# RTDsSheet3.net
KiCad netlist of a schematic drawn in Altium Designer
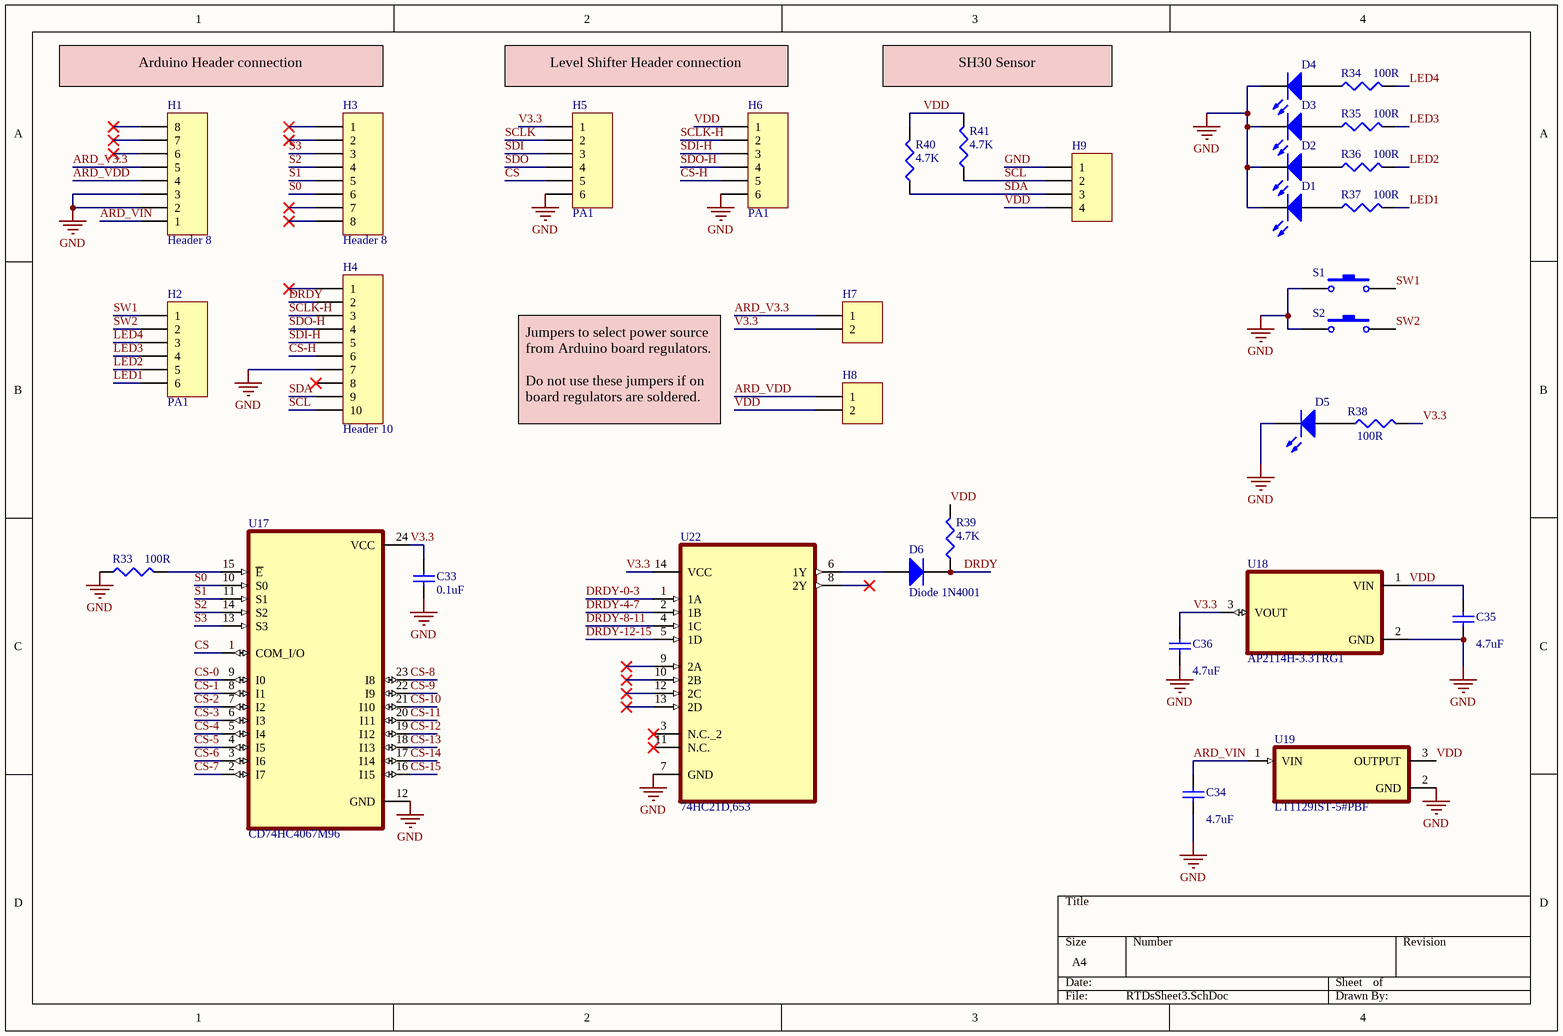
[diagram p0: RTDsSheet3.SchDoc]

(export (version "E")
  (design (tool "Eeschema 10.0.6"))
  (components
    (comp (ref "C33")
      (value "0.1uF")
      (footprint "1608[0603]")
      (description "Capacitor (Semiconductor SIM Model)")
      (fields (field (name "PUBLISHER") "Altium Limited"))
      (libsource (lib "Miscellaneous Devices") (part "Cap Semi"))
    )
    (comp (ref "C34")
      (value "4.7uF")
      (footprint "C0805")
      (description "Capacitor (Semiconductor SIM Model)")
      (fields (field (name "PUBLISHER") "Altium Limited"))
      (libsource (lib "Miscellaneous Devices") (part "Cap Semi"))
    )
    (comp (ref "C35")
      (value "4.7uF")
      (footprint "C0805")
      (description "Capacitor (Semiconductor SIM Model)")
      (fields (field (name "PUBLISHER") "Altium Limited"))
      (libsource (lib "Miscellaneous Devices") (part "Cap Semi"))
    )
    (comp (ref "C36")
      (value "4.7uF")
      (footprint "C0805")
      (description "Capacitor (Semiconductor SIM Model)")
      (fields (field (name "PUBLISHER") "Altium Limited"))
      (libsource (lib "Miscellaneous Devices") (part "Cap Semi"))
    )
    (comp (ref "D1")
      (value "~")
      (footprint "6-0805_N")
      (description "Typical BLUE SiC LED")
      (fields (field (name "PUBLISHER") "Altium Limited"))
      (libsource (lib "Miscellaneous Devices") (part "LED3"))
    )
    (comp (ref "D2")
      (value "~")
      (footprint "6-0805_N")
      (description "Typical BLUE SiC LED")
      (fields (field (name "PUBLISHER") "Altium Limited"))
      (libsource (lib "Miscellaneous Devices") (part "LED3"))
    )
    (comp (ref "D3")
      (value "~")
      (footprint "6-0805_N")
      (description "Typical BLUE SiC LED")
      (fields (field (name "PUBLISHER") "Altium Limited"))
      (libsource (lib "Miscellaneous Devices") (part "LED3"))
    )
    (comp (ref "D4")
      (value "~")
      (footprint "6-0805_N")
      (description "Typical BLUE SiC LED")
      (fields (field (name "PUBLISHER") "Altium Limited"))
      (libsource (lib "Miscellaneous Devices") (part "LED3"))
    )
    (comp (ref "D5")
      (value "~")
      (footprint "6-0805_N")
      (description "Typical BLUE SiC LED")
      (fields (field (name "PUBLISHER") "Altium Limited"))
      (libsource (lib "Miscellaneous Devices") (part "LED3"))
    )
    (comp (ref "D6")
      (value "Diode 1N4001")
      (footprint "C0805")
      (description "1 Amp General Purpose Rectifier")
      (fields (field (name "PUBLISHER") "Altium Limited"))
      (libsource (lib "Miscellaneous Devices") (part "Diode 1N4001"))
    )
    (comp (ref "H1")
      (value "Header 8")
      (footprint "HDR1X8")
      (description "Header, 8-Pin")
      (fields (field (name "PUBLISHER") "Altium Limited"))
      (libsource (lib "Miscellaneous Connectors") (part "Header 8"))
    )
    (comp (ref "H2")
      (value "PA1")
      (footprint "HDR1X6")
      (description "Header, 6-Pin")
      (fields (field (name "PUBLISHER") "Altium Limited"))
      (libsource (lib "Miscellaneous Connectors") (part "Header 6"))
    )
    (comp (ref "H3")
      (value "Header 8")
      (footprint "HDR1X8")
      (description "Header, 8-Pin")
      (fields (field (name "PUBLISHER") "Altium Limited"))
      (libsource (lib "") (part "Header 8_1"))
    )
    (comp (ref "H4")
      (value "Header 10")
      (footprint "HDR1X10")
      (description "Header, 10-Pin")
      (fields (field (name "PUBLISHER") "Altium Limited"))
      (libsource (lib "Miscellaneous Connectors") (part "Header 10"))
    )
    (comp (ref "H5")
      (value "PA1")
      (footprint "HDR1X6")
      (description "Header, 6-Pin")
      (fields (field (name "PUBLISHER") "Altium Limited"))
      (libsource (lib "Miscellaneous Connectors") (part "Header 6"))
    )
    (comp (ref "H6")
      (value "PA1")
      (footprint "HDR1X6")
      (description "Header, 6-Pin")
      (fields (field (name "PUBLISHER") "Altium Limited"))
      (libsource (lib "Miscellaneous Connectors") (part "Header 6"))
    )
    (comp (ref "H7")
      (value "~")
      (footprint "HDR1X2")
      (description "Header, 2-Pin")
      (fields (field (name "PUBLISHER") "Altium Limited"))
      (libsource (lib "Miscellaneous Connectors") (part "Header 2"))
    )
    (comp (ref "H8")
      (value "~")
      (footprint "HDR1X2")
      (description "Header, 2-Pin")
      (fields (field (name "PUBLISHER") "Altium Limited"))
      (libsource (lib "Miscellaneous Connectors") (part "Header 2"))
    )
    (comp (ref "H9")
      (value "~")
      (footprint "HDR1X4")
      (description "Header, 4-Pin")
      (fields (field (name "PUBLISHER") "Altium Limited"))
      (libsource (lib "Miscellaneous Connectors") (part "Header 4"))
    )
    (comp (ref "R33")
      (value "100R")
      (footprint "J1-0603")
      (description "Resistor")
      (fields (field (name "PUBLISHER") "Altium Limited"))
      (libsource (lib "Miscellaneous Devices") (part "Res3"))
    )
    (comp (ref "R34")
      (value "100R")
      (footprint "J1-0603")
      (description "Resistor")
      (fields (field (name "PUBLISHER") "Altium Limited"))
      (libsource (lib "Miscellaneous Devices") (part "Res3"))
    )
    (comp (ref "R35")
      (value "100R")
      (footprint "J1-0603")
      (description "Resistor")
      (fields (field (name "PUBLISHER") "Altium Limited"))
      (libsource (lib "Miscellaneous Devices") (part "Res3"))
    )
    (comp (ref "R36")
      (value "100R")
      (footprint "J1-0603")
      (description "Resistor")
      (fields (field (name "PUBLISHER") "Altium Limited"))
      (libsource (lib "Miscellaneous Devices") (part "Res3"))
    )
    (comp (ref "R37")
      (value "100R")
      (footprint "J1-0603")
      (description "Resistor")
      (fields (field (name "PUBLISHER") "Altium Limited"))
      (libsource (lib "Miscellaneous Devices") (part "Res3"))
    )
    (comp (ref "R38")
      (value "100R")
      (footprint "J1-0603")
      (description "Resistor")
      (fields (field (name "PUBLISHER") "Altium Limited"))
      (libsource (lib "Miscellaneous Devices") (part "Res3"))
    )
    (comp (ref "R39")
      (value "4.7K")
      (footprint "J1-0603")
      (description "Resistor")
      (fields (field (name "PUBLISHER") "Altium Limited"))
      (libsource (lib "Miscellaneous Devices") (part "Res3"))
    )
    (comp (ref "R40")
      (value "4.7K")
      (footprint "J1-0603")
      (description "Resistor")
      (fields (field (name "PUBLISHER") "Altium Limited"))
      (libsource (lib "Miscellaneous Devices") (part "Res3"))
    )
    (comp (ref "R41")
      (value "4.7K")
      (footprint "J1-0603")
      (description "Resistor")
      (fields (field (name "PUBLISHER") "Altium Limited"))
      (libsource (lib "Miscellaneous Devices") (part "Res3"))
    )
    (comp (ref "S1")
      (value "~")
      (footprint "PTS525SM08SMTR2LFS")
      (description "Switch")
      (fields (field (name "PUBLISHER") "Altium Limited"))
      (libsource (lib "Miscellaneous Devices") (part "SW-PB"))
    )
    (comp (ref "S2")
      (value "~")
      (footprint "PTS525SM08SMTR2LFS")
      (description "Switch")
      (fields (field (name "PUBLISHER") "Altium Limited"))
      (libsource (lib "Miscellaneous Devices") (part "SW-PB"))
    )
    (comp (ref "U17")
      (value "CD74HC4067M96")
      (footprint "CD74HC4067M96:SOIC127P1030X265-24N")
      (fields (field (name "MF") "{'manufacturer': u'Texas Instruments'}"))
      (libsource (lib "*") (part "CD74HC4067M96"))
    )
    (comp (ref "U18")
      (value "AP2114H-3.3TRG1")
      (footprint "SOT230P700X180-4N")
      (fields (field (name "MF") "{'manufacturer': u'Diodes Inc.'}"))
      (libsource (lib "*") (part "AP2114H-3.3TRG1"))
    )
    (comp (ref "U19")
      (value "LT1129IST-5#PBF")
      (footprint "LT1129IST-5#PBF:SOT230P700X180-4N")
      (fields (field (name "MF") "{'manufacturer': u'Analog Devices'}"))
      (libsource (lib "LT1129IST-5#PBF") (part "LT1129IST-5#PBF"))
    )
    (comp (ref "U22")
      (value "74HC21D,653")
      (footprint "74HC21D,653:SOIC127P600X175-14N")
      (description "Dual 4-input AND gate")
      (fields (field (name "MF") "{'manufacturer': u'Nexperia USA'}"))
      (libsource (lib "*") (part "74HC21D,653"))
    )
  )
  (nets
    (net (code "1") (name "/ARD_V3.3") (class "Default")
      (node (ref "H1") (pin "5") (pinfunction "5_5") (pintype "passive"))
      (node (ref "H7") (pin "1") (pinfunction "1_1") (pintype "passive"))
    )
    (net (code "2") (name "/ARD_VDD") (class "Default")
      (node (ref "H1") (pin "4") (pinfunction "4_4") (pintype "passive"))
      (node (ref "H8") (pin "1") (pinfunction "1_1") (pintype "passive"))
    )
    (net (code "3") (name "/ARD_VIN") (class "Default")
      (node (ref "C34") (pin "2") (pinfunction "2_2") (pintype "passive"))
      (node (ref "H1") (pin "1") (pinfunction "1_1") (pintype "passive"))
      (node (ref "U19") (pin "1") (pinfunction "VIN_1") (pintype "input"))
    )
    (net (code "4") (name "/CS") (class "Default")
      (node (ref "H5") (pin "5") (pinfunction "5_5") (pintype "passive"))
      (node (ref "U17") (pin "1") (pinfunction "COM_I/O_1") (pintype "bidirectional"))
    )
    (net (code "5") (name "/CS-0") (class "Default")
      (node (ref "U17") (pin "9") (pinfunction "I0_9") (pintype "bidirectional"))
    )
    (net (code "6") (name "/CS-1") (class "Default")
      (node (ref "U17") (pin "8") (pinfunction "I1_8") (pintype "bidirectional"))
    )
    (net (code "7") (name "/CS-2") (class "Default")
      (node (ref "U17") (pin "7") (pinfunction "I2_7") (pintype "bidirectional"))
    )
    (net (code "8") (name "/CS-3") (class "Default")
      (node (ref "U17") (pin "6") (pinfunction "I3_6") (pintype "bidirectional"))
    )
    (net (code "9") (name "/CS-4") (class "Default")
      (node (ref "U17") (pin "5") (pinfunction "I4_5") (pintype "bidirectional"))
    )
    (net (code "10") (name "/CS-5") (class "Default")
      (node (ref "U17") (pin "4") (pinfunction "I5_4") (pintype "bidirectional"))
    )
    (net (code "11") (name "/CS-6") (class "Default")
      (node (ref "U17") (pin "3") (pinfunction "I6_3") (pintype "bidirectional"))
    )
    (net (code "12") (name "/CS-7") (class "Default")
      (node (ref "U17") (pin "2") (pinfunction "I7_2") (pintype "bidirectional"))
    )
    (net (code "13") (name "/CS-8") (class "Default")
      (node (ref "U17") (pin "23") (pinfunction "I8_23") (pintype "bidirectional"))
    )
    (net (code "14") (name "/CS-9") (class "Default")
      (node (ref "U17") (pin "22") (pinfunction "I9_22") (pintype "bidirectional"))
    )
    (net (code "15") (name "/CS-10") (class "Default")
      (node (ref "U17") (pin "21") (pinfunction "I10_21") (pintype "bidirectional"))
    )
    (net (code "16") (name "/CS-11") (class "Default")
      (node (ref "U17") (pin "20") (pinfunction "I11_20") (pintype "bidirectional"))
    )
    (net (code "17") (name "/CS-12") (class "Default")
      (node (ref "U17") (pin "19") (pinfunction "I12_19") (pintype "bidirectional"))
    )
    (net (code "18") (name "/CS-13") (class "Default")
      (node (ref "U17") (pin "18") (pinfunction "I13_18") (pintype "bidirectional"))
    )
    (net (code "19") (name "/CS-14") (class "Default")
      (node (ref "U17") (pin "17") (pinfunction "I14_17") (pintype "bidirectional"))
    )
    (net (code "20") (name "/CS-15") (class "Default")
      (node (ref "U17") (pin "16") (pinfunction "I15_16") (pintype "bidirectional"))
    )
    (net (code "21") (name "/CS-H") (class "Default")
      (node (ref "H4") (pin "6") (pinfunction "6_6") (pintype "passive"))
      (node (ref "H6") (pin "5") (pinfunction "5_5") (pintype "passive"))
    )
    (net (code "22") (name "/DRDY") (class "Default")
      (node (ref "D6") (pin "2") (pinfunction "K_2") (pintype "passive"))
      (node (ref "H4") (pin "2") (pinfunction "2_2") (pintype "passive"))
      (node (ref "R39") (pin "2") (pinfunction "2_2") (pintype "passive"))
    )
    (net (code "23") (name "/DRDY-0-3") (class "Default")
      (node (ref "U22") (pin "1") (pinfunction "1A_1") (pintype "input"))
    )
    (net (code "24") (name "/DRDY-4-7") (class "Default")
      (node (ref "U22") (pin "2") (pinfunction "1B_2") (pintype "input"))
    )
    (net (code "25") (name "/DRDY-8-11") (class "Default")
      (node (ref "U22") (pin "4") (pinfunction "1C_4") (pintype "input"))
    )
    (net (code "26") (name "/DRDY-12-15") (class "Default")
      (node (ref "U22") (pin "5") (pinfunction "1D_5") (pintype "input"))
    )
    (net (code "27") (name "/LED1") (class "Default")
      (node (ref "H2") (pin "6") (pinfunction "6_6") (pintype "passive"))
      (node (ref "R37") (pin "1") (pinfunction "1_1") (pintype "passive"))
    )
    (net (code "28") (name "/LED2") (class "Default")
      (node (ref "H2") (pin "5") (pinfunction "5_5") (pintype "passive"))
      (node (ref "R36") (pin "1") (pinfunction "1_1") (pintype "passive"))
    )
    (net (code "29") (name "/LED3") (class "Default")
      (node (ref "H2") (pin "4") (pinfunction "4_4") (pintype "passive"))
      (node (ref "R35") (pin "1") (pinfunction "1_1") (pintype "passive"))
    )
    (net (code "30") (name "/LED4") (class "Default")
      (node (ref "H2") (pin "3") (pinfunction "3_3") (pintype "passive"))
      (node (ref "R34") (pin "1") (pinfunction "1_1") (pintype "passive"))
    )
    (net (code "31") (name "/S0") (class "Default")
      (node (ref "H3") (pin "6") (pinfunction "6_6") (pintype "passive"))
      (node (ref "U17") (pin "10") (pinfunction "S0_10") (pintype "input"))
    )
    (net (code "32") (name "/S1") (class "Default")
      (node (ref "H3") (pin "5") (pinfunction "5_5") (pintype "passive"))
      (node (ref "U17") (pin "11") (pinfunction "S1_11") (pintype "input"))
    )
    (net (code "33") (name "/S2") (class "Default")
      (node (ref "H3") (pin "4") (pinfunction "4_4") (pintype "passive"))
      (node (ref "U17") (pin "14") (pinfunction "S2_14") (pintype "input"))
    )
    (net (code "34") (name "/S3") (class "Default")
      (node (ref "H3") (pin "3") (pinfunction "3_3") (pintype "passive"))
      (node (ref "U17") (pin "13") (pinfunction "S3_13") (pintype "input"))
    )
    (net (code "35") (name "/SCL") (class "Default")
      (node (ref "H4") (pin "10") (pinfunction "10_10") (pintype "passive"))
      (node (ref "H9") (pin "2") (pinfunction "2_2") (pintype "passive"))
      (node (ref "R41") (pin "2") (pinfunction "2_2") (pintype "passive"))
    )
    (net (code "36") (name "/SCLK") (class "Default")
      (node (ref "H5") (pin "2") (pinfunction "2_2") (pintype "passive"))
    )
    (net (code "37") (name "/SCLK-H") (class "Default")
      (node (ref "H4") (pin "3") (pinfunction "3_3") (pintype "passive"))
      (node (ref "H6") (pin "2") (pinfunction "2_2") (pintype "passive"))
    )
    (net (code "38") (name "/SDA") (class "Default")
      (node (ref "H4") (pin "9") (pinfunction "9_9") (pintype "passive"))
      (node (ref "H9") (pin "3") (pinfunction "3_3") (pintype "passive"))
      (node (ref "R40") (pin "2") (pinfunction "2_2") (pintype "passive"))
    )
    (net (code "39") (name "/SDI") (class "Default")
      (node (ref "H5") (pin "3") (pinfunction "3_3") (pintype "passive"))
    )
    (net (code "40") (name "/SDI-H") (class "Default")
      (node (ref "H4") (pin "5") (pinfunction "5_5") (pintype "passive"))
      (node (ref "H6") (pin "3") (pinfunction "3_3") (pintype "passive"))
    )
    (net (code "41") (name "/SDO") (class "Default")
      (node (ref "H5") (pin "4") (pinfunction "4_4") (pintype "passive"))
    )
    (net (code "42") (name "/SDO-H") (class "Default")
      (node (ref "H4") (pin "4") (pinfunction "4_4") (pintype "passive"))
      (node (ref "H6") (pin "4") (pinfunction "4_4") (pintype "passive"))
    )
    (net (code "43") (name "/SW1") (class "Default")
      (node (ref "H2") (pin "1") (pinfunction "1_1") (pintype "passive"))
      (node (ref "S1") (pin "2") (pinfunction "2_2") (pintype "passive"))
    )
    (net (code "44") (name "/SW2") (class "Default")
      (node (ref "H2") (pin "2") (pinfunction "2_2") (pintype "passive"))
      (node (ref "S2") (pin "2") (pinfunction "2_2") (pintype "passive"))
    )
    (net (code "45") (name "/V3.3") (class "Default")
      (node (ref "C33") (pin "1") (pinfunction "1_1") (pintype "passive"))
      (node (ref "C36") (pin "2") (pinfunction "2_2") (pintype "passive"))
      (node (ref "H5") (pin "1") (pinfunction "1_1") (pintype "passive"))
      (node (ref "H7") (pin "2") (pinfunction "2_2") (pintype "passive"))
      (node (ref "R38") (pin "1") (pinfunction "1_1") (pintype "passive"))
      (node (ref "U17") (pin "24") (pinfunction "VCC_24") (pintype "power_in"))
      (node (ref "U18") (pin "3") (pinfunction "VOUT_3") (pintype "bidirectional"))
      (node (ref "U22") (pin "14") (pinfunction "VCC_14") (pintype "power_in"))
    )
    (net (code "46") (name "/VDD") (class "Default")
      (node (ref "C35") (pin "2") (pinfunction "2_2") (pintype "passive"))
      (node (ref "H6") (pin "1") (pinfunction "1_1") (pintype "passive"))
      (node (ref "H8") (pin "2") (pinfunction "2_2") (pintype "passive"))
      (node (ref "H9") (pin "4") (pinfunction "4_4") (pintype "passive"))
      (node (ref "R39") (pin "1") (pinfunction "1_1") (pintype "passive"))
      (node (ref "R40") (pin "1") (pinfunction "1_1") (pintype "passive"))
      (node (ref "R41") (pin "1") (pinfunction "1_1") (pintype "passive"))
      (node (ref "U18") (pin "1") (pinfunction "VIN_1") (pintype "power_in"))
      (node (ref "U19") (pin "3") (pinfunction "OUTPUT_3") (pintype "power_in"))
    )
    (net (code "47") (name "GND") (class "Default")
      (node (ref "C33") (pin "2") (pinfunction "2_2") (pintype "passive"))
      (node (ref "C34") (pin "1") (pinfunction "1_1") (pintype "passive"))
      (node (ref "C35") (pin "1") (pinfunction "1_1") (pintype "passive"))
      (node (ref "C36") (pin "1") (pinfunction "1_1") (pintype "passive"))
      (node (ref "D1") (pin "2") (pinfunction "K_2") (pintype "passive"))
      (node (ref "D2") (pin "2") (pinfunction "K_2") (pintype "passive"))
      (node (ref "D3") (pin "2") (pinfunction "K_2") (pintype "passive"))
      (node (ref "D4") (pin "2") (pinfunction "K_2") (pintype "passive"))
      (node (ref "D5") (pin "2") (pinfunction "K_2") (pintype "passive"))
      (node (ref "H1") (pin "2") (pinfunction "2_2") (pintype "passive"))
      (node (ref "H1") (pin "3") (pinfunction "3_3") (pintype "passive"))
      (node (ref "H4") (pin "7") (pinfunction "7_7") (pintype "passive"))
      (node (ref "H5") (pin "6") (pinfunction "6_6") (pintype "passive"))
      (node (ref "H6") (pin "6") (pinfunction "6_6") (pintype "passive"))
      (node (ref "H9") (pin "1") (pinfunction "1_1") (pintype "passive"))
      (node (ref "R33") (pin "2") (pinfunction "2_2") (pintype "passive"))
      (node (ref "S1") (pin "1") (pinfunction "1_1") (pintype "passive"))
      (node (ref "S2") (pin "1") (pinfunction "1_1") (pintype "passive"))
      (node (ref "U17") (pin "12") (pinfunction "GND_12") (pintype "power_in"))
      (node (ref "U18") (pin "2") (pinfunction "GND_2") (pintype "power_in"))
      (node (ref "U19") (pin "2") (pinfunction "GND_2") (pintype "power_in"))
      (node (ref "U22") (pin "7") (pinfunction "GND_7") (pintype "passive"))
    )
    (net (code "48") (name "Net-(D1-A)") (class "Default")
      (node (ref "D1") (pin "1") (pinfunction "A_1") (pintype "passive"))
      (node (ref "R37") (pin "2") (pinfunction "2_2") (pintype "passive"))
    )
    (net (code "49") (name "Net-(D2-A)") (class "Default")
      (node (ref "D2") (pin "1") (pinfunction "A_1") (pintype "passive"))
      (node (ref "R36") (pin "2") (pinfunction "2_2") (pintype "passive"))
    )
    (net (code "50") (name "Net-(D3-A)") (class "Default")
      (node (ref "D3") (pin "1") (pinfunction "A_1") (pintype "passive"))
      (node (ref "R35") (pin "2") (pinfunction "2_2") (pintype "passive"))
    )
    (net (code "51") (name "Net-(D4-A)") (class "Default")
      (node (ref "D4") (pin "1") (pinfunction "A_1") (pintype "passive"))
      (node (ref "R34") (pin "2") (pinfunction "2_2") (pintype "passive"))
    )
    (net (code "52") (name "Net-(D5-A)") (class "Default")
      (node (ref "D5") (pin "1") (pinfunction "A_1") (pintype "passive"))
      (node (ref "R38") (pin "2") (pinfunction "2_2") (pintype "passive"))
    )
    (net (code "53") (name "Net-(D6-A)") (class "Default")
      (node (ref "D6") (pin "1") (pinfunction "A_1") (pintype "passive"))
      (node (ref "U22") (pin "6") (pinfunction "1Y_6") (pintype "output"))
    )
    (net (code "54") (name "Net-(U17-~{E})") (class "Default")
      (node (ref "R33") (pin "1") (pinfunction "1_1") (pintype "passive"))
      (node (ref "U17") (pin "15") (pinfunction "~{E}_15") (pintype "input"))
    )
    (net (code "55") (name "unconnected-(H1-Pad6)") (class "Default")
      (node (ref "H1") (pin "6") (pinfunction "6_6") (pintype "passive+no_connect"))
    )
    (net (code "56") (name "unconnected-(H1-Pad7)") (class "Default")
      (node (ref "H1") (pin "7") (pinfunction "7_7") (pintype "passive+no_connect"))
    )
    (net (code "57") (name "unconnected-(H1-Pad8)") (class "Default")
      (node (ref "H1") (pin "8") (pinfunction "8_8") (pintype "passive+no_connect"))
    )
    (net (code "58") (name "unconnected-(H3-Pad1)") (class "Default")
      (node (ref "H3") (pin "1") (pinfunction "1_1") (pintype "passive+no_connect"))
    )
    (net (code "59") (name "unconnected-(H3-Pad2)") (class "Default")
      (node (ref "H3") (pin "2") (pinfunction "2_2") (pintype "passive+no_connect"))
    )
    (net (code "60") (name "unconnected-(H3-Pad7)") (class "Default")
      (node (ref "H3") (pin "7") (pinfunction "7_7") (pintype "passive+no_connect"))
    )
    (net (code "61") (name "unconnected-(H3-Pad8)") (class "Default")
      (node (ref "H3") (pin "8") (pinfunction "8_8") (pintype "passive+no_connect"))
    )
    (net (code "62") (name "unconnected-(H4-Pad1)") (class "Default")
      (node (ref "H4") (pin "1") (pinfunction "1_1") (pintype "passive+no_connect"))
    )
    (net (code "63") (name "unconnected-(H4-Pad8)") (class "Default")
      (node (ref "H4") (pin "8") (pinfunction "8_8") (pintype "passive+no_connect"))
    )
    (net (code "64") (name "unconnected-(U22-2A-Pad9)") (class "Default")
      (node (ref "U22") (pin "9") (pinfunction "2A_9") (pintype "input+no_connect"))
    )
    (net (code "65") (name "unconnected-(U22-2B-Pad10)") (class "Default")
      (node (ref "U22") (pin "10") (pinfunction "2B_10") (pintype "input+no_connect"))
    )
    (net (code "66") (name "unconnected-(U22-2C-Pad12)") (class "Default")
      (node (ref "U22") (pin "12") (pinfunction "2C_12") (pintype "input+no_connect"))
    )
    (net (code "67") (name "unconnected-(U22-2D-Pad13)") (class "Default")
      (node (ref "U22") (pin "13") (pinfunction "2D_13") (pintype "input+no_connect"))
    )
    (net (code "68") (name "unconnected-(U22-2Y-Pad8)") (class "Default")
      (node (ref "U22") (pin "8") (pinfunction "2Y_8") (pintype "output+no_connect"))
    )
    (net (code "69") (name "unconnected-(U22-N.C.-Pad11)") (class "Default")
      (node (ref "U22") (pin "11") (pinfunction "N.C._11") (pintype "passive+no_connect"))
    )
    (net (code "70") (name "unconnected-(U22-N.C._2-Pad3)") (class "Default")
      (node (ref "U22") (pin "3") (pinfunction "N.C._2_3") (pintype "passive+no_connect"))
    )
  )
)
